# Pr_tica-14.net
KiCad netlist of a schematic drawn in EasyEDA
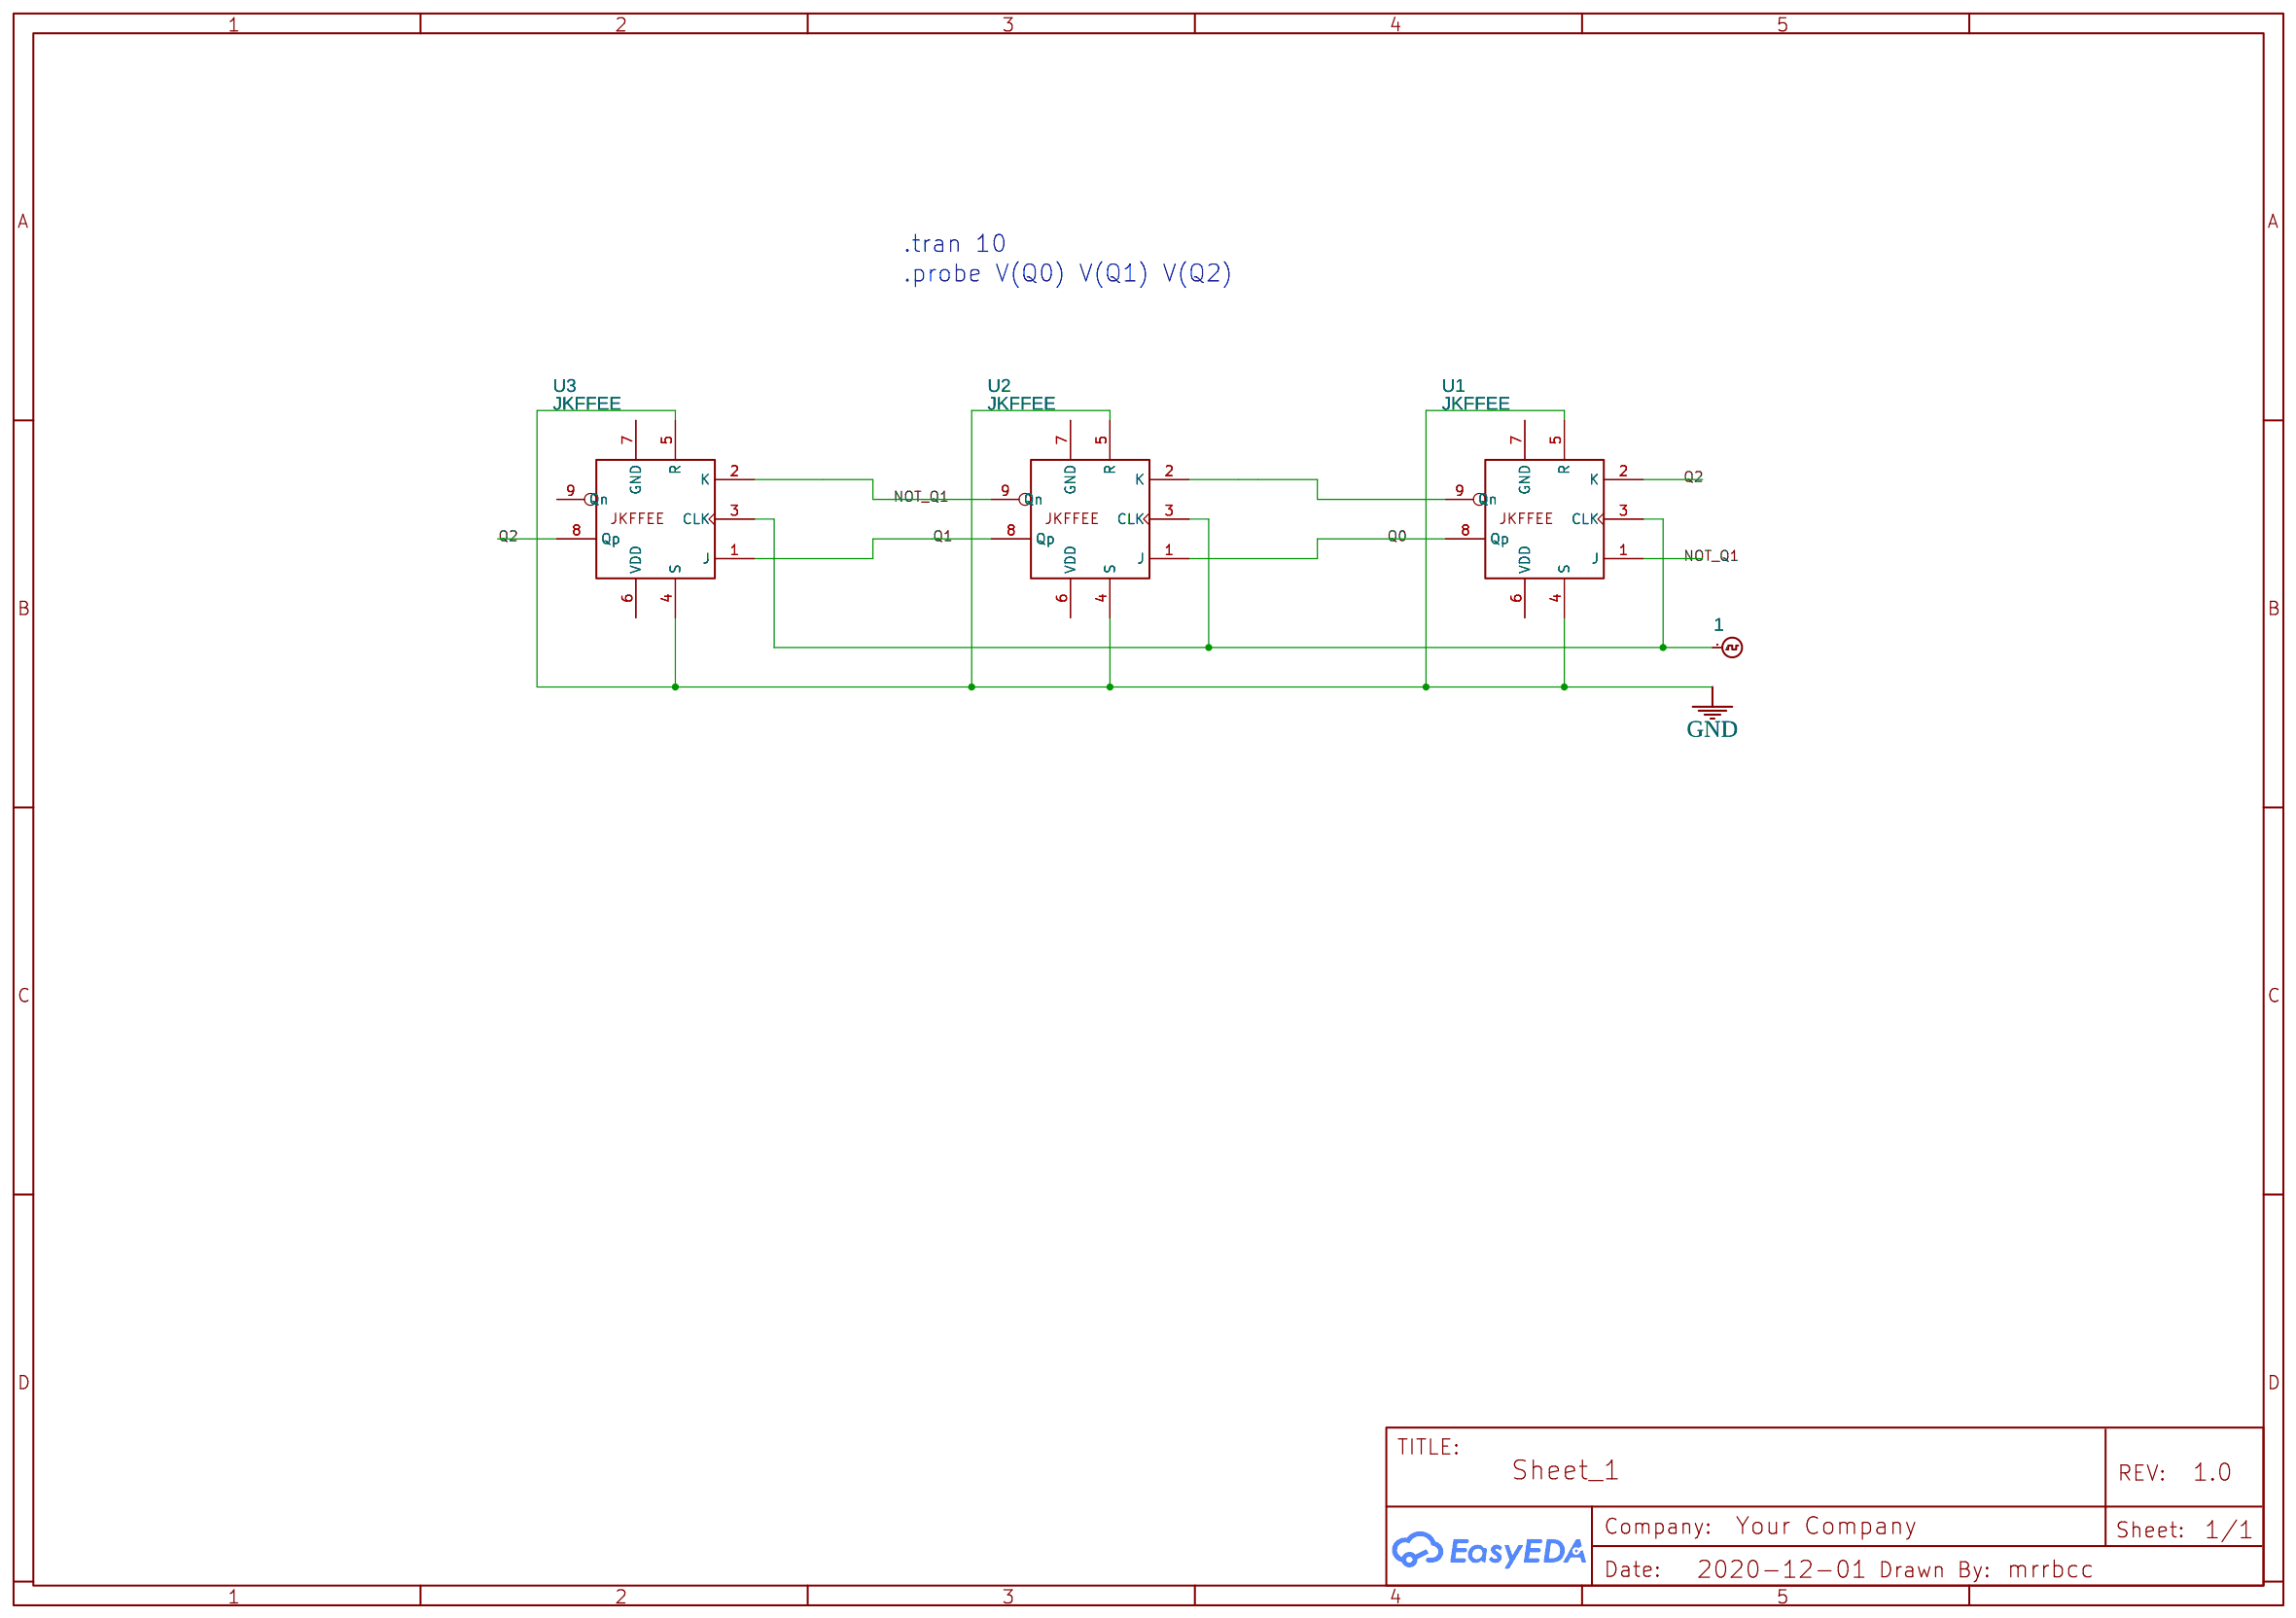
[diagram p0: schematic sheet]

(export (version "E")
  (design (tool "Eeschema 10.0.6"))
  (components
    (comp (ref "U1") (value "JKFFEE") (libsource (lib "") (part "LOGIC")))
    (comp (ref "U2") (value "JKFFEE") (libsource (lib "") (part "LOGIC")))
    (comp (ref "U3") (value "JKFFEE") (libsource (lib "") (part "LOGIC")))
    (comp (ref "U4") (value "1") (libsource (lib "") (part "DIGITALCLOCK")))
  )
  (nets
    (net (code "1") (name "/NOT_Q1") (class "Default")
      (node (ref "U1") (pin "1") (pinfunction "J_1") (pintype "unspecified"))
      (node (ref "U2") (pin "9") (pinfunction "Qn_9") (pintype "unspecified"))
      (node (ref "U3") (pin "2") (pinfunction "K_2") (pintype "unspecified"))
    )
    (net (code "2") (name "/Q0") (class "Default")
      (node (ref "U1") (pin "8") (pinfunction "Qp_8") (pintype "unspecified"))
      (node (ref "U2") (pin "1") (pinfunction "J_1") (pintype "unspecified"))
    )
    (net (code "3") (name "/Q1") (class "Default")
      (node (ref "U2") (pin "8") (pinfunction "Qp_8") (pintype "unspecified"))
      (node (ref "U3") (pin "1") (pinfunction "J_1") (pintype "unspecified"))
    )
    (net (code "4") (name "/Q2") (class "Default")
      (node (ref "U1") (pin "2") (pinfunction "K_2") (pintype "unspecified"))
      (node (ref "U3") (pin "8") (pinfunction "Qp_8") (pintype "unspecified"))
    )
    (net (code "5") (name "GND") (class "Default")
      (node (ref "U1") (pin "4") (pinfunction "S_4") (pintype "unspecified"))
      (node (ref "U1") (pin "5") (pinfunction "R_5") (pintype "unspecified"))
      (node (ref "U2") (pin "4") (pinfunction "S_4") (pintype "unspecified"))
      (node (ref "U2") (pin "5") (pinfunction "R_5") (pintype "unspecified"))
      (node (ref "U3") (pin "4") (pinfunction "S_4") (pintype "unspecified"))
      (node (ref "U3") (pin "5") (pinfunction "R_5") (pintype "unspecified"))
    )
    (net (code "6") (name "Net-(U1-CLK)") (class "Default")
      (node (ref "U1") (pin "3") (pinfunction "CLK_3") (pintype "unspecified"))
      (node (ref "U2") (pin "3") (pinfunction "CLK_3") (pintype "unspecified"))
      (node (ref "U3") (pin "3") (pinfunction "CLK_3") (pintype "unspecified"))
      (node (ref "U4") (pin "1") (pinfunction "1_1") (pintype "unspecified"))
    )
    (net (code "7") (name "Net-(U1-Qn)") (class "Default")
      (node (ref "U1") (pin "9") (pinfunction "Qn_9") (pintype "unspecified"))
      (node (ref "U2") (pin "2") (pinfunction "K_2") (pintype "unspecified"))
    )
    (net (code "8") (name "unconnected-(U1-GND-Pad7)") (class "Default")
      (node (ref "U1") (pin "7") (pinfunction "GND_7") (pintype "unspecified"))
    )
    (net (code "9") (name "unconnected-(U1-VDD-Pad6)") (class "Default")
      (node (ref "U1") (pin "6") (pinfunction "VDD_6") (pintype "unspecified"))
    )
    (net (code "10") (name "unconnected-(U2-GND-Pad7)") (class "Default")
      (node (ref "U2") (pin "7") (pinfunction "GND_7") (pintype "unspecified"))
    )
    (net (code "11") (name "unconnected-(U2-VDD-Pad6)") (class "Default")
      (node (ref "U2") (pin "6") (pinfunction "VDD_6") (pintype "unspecified"))
    )
    (net (code "12") (name "unconnected-(U3-GND-Pad7)") (class "Default")
      (node (ref "U3") (pin "7") (pinfunction "GND_7") (pintype "unspecified"))
    )
    (net (code "13") (name "unconnected-(U3-Qn-Pad9)") (class "Default")
      (node (ref "U3") (pin "9") (pinfunction "Qn_9") (pintype "unspecified"))
    )
    (net (code "14") (name "unconnected-(U3-VDD-Pad6)") (class "Default")
      (node (ref "U3") (pin "6") (pinfunction "VDD_6") (pintype "unspecified"))
    )
  )
)
